# MCU_-_Peripherals.net
KiCad netlist of a schematic drawn in Altium Designer
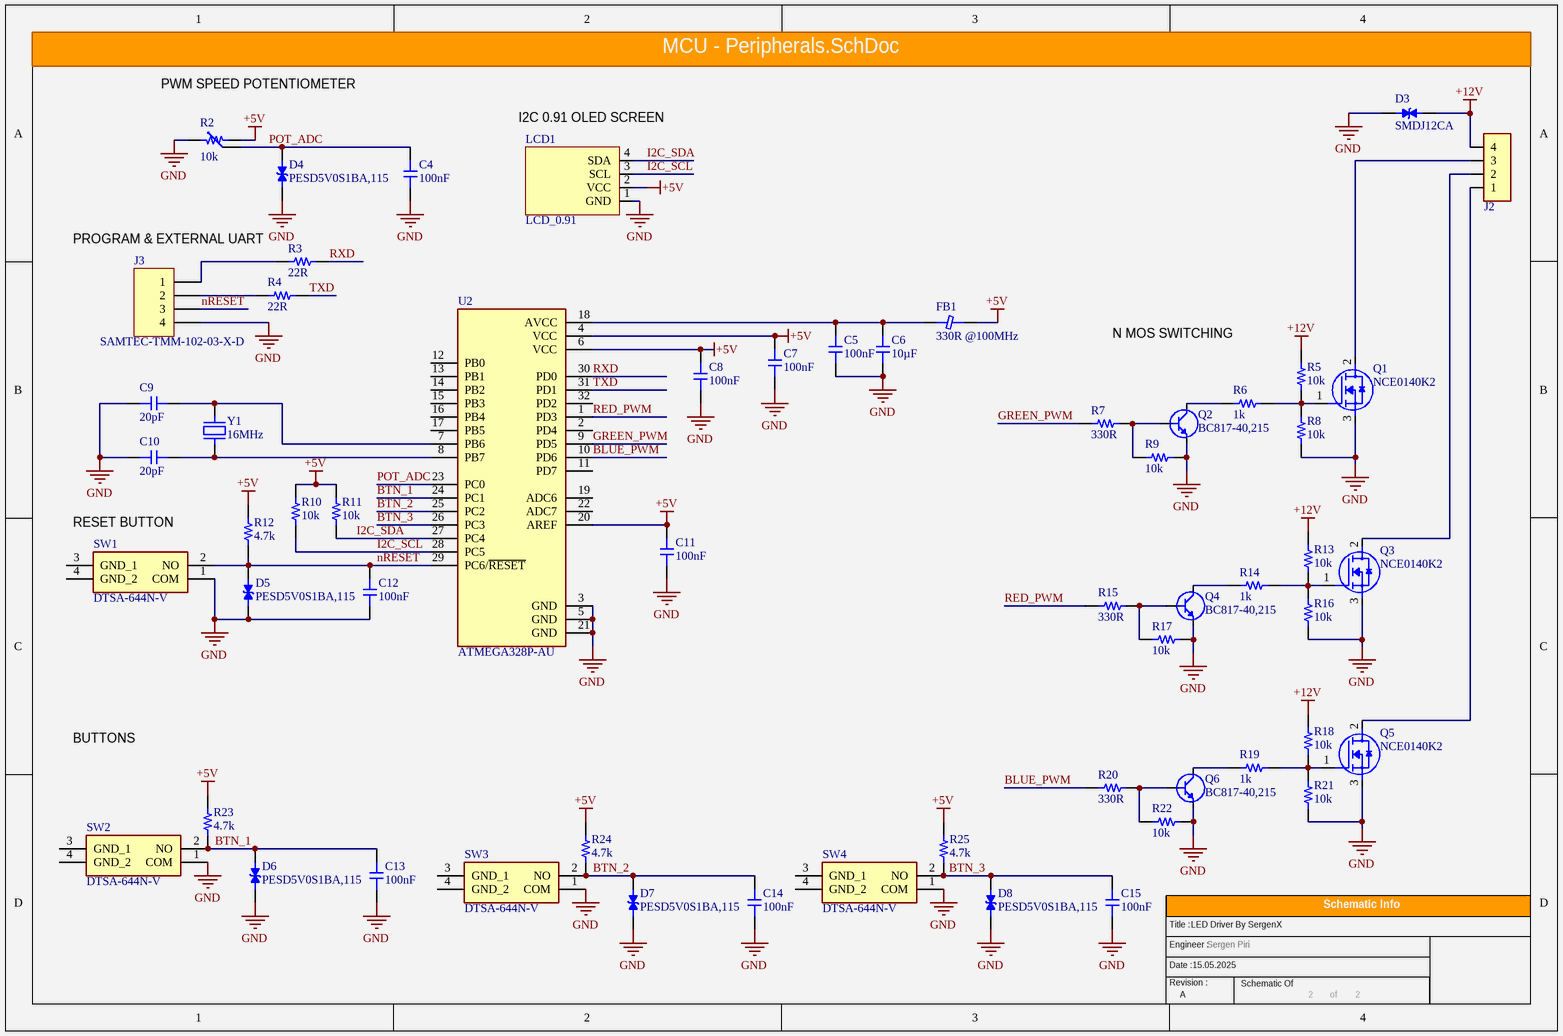
[diagram p0: MCU - Peripherals.SchDoc]

(export (version "E")
  (design (tool "Eeschema 10.0.6"))
  (components
    (comp (ref "C4")
      (value "100nF")
      (footprint "0402_CAP")
      (description "MLCC (1005) 0402 100nF 16VDC ±10% X7R")
      (libsource (lib "MainLibrary") (part "CL05B104KO5NNNC"))
    )
    (comp (ref "C5")
      (value "100nF")
      (footprint "0402_CAP")
      (description "MLCC (1005) 0402 100nF 16VDC ±10% X7R")
      (libsource (lib "MainLibrary") (part "CL05B104KO5NNNC"))
    )
    (comp (ref "C6")
      (value "10µF")
      (footprint "0805")
      (description "MLCC (2012) 0805 10uF 35VDC ±10% X6S")
      (libsource (lib "MainLibrary") (part "GRM21BC8YA106KE11L_1"))
    )
    (comp (ref "C7")
      (value "100nF")
      (footprint "0402_CAP")
      (description "MLCC (1005) 0402 100nF 16VDC ±10% X7R")
      (libsource (lib "MainLibrary") (part "CL05B104KO5NNNC"))
    )
    (comp (ref "C8")
      (value "100nF")
      (footprint "0402_CAP")
      (description "MLCC (1005) 0402 100nF 16VDC ±10% X7R")
      (libsource (lib "MainLibrary") (part "CL05B104KO5NNNC"))
    )
    (comp (ref "C9")
      (value "20pF")
      (footprint "0402_CAP")
      (description "MLCC (1005) 0402 20pF 50VDC ±5% C0G (NP0)")
      (libsource (lib "MainLibrary") (part "CL05C200JB5NNNC"))
    )
    (comp (ref "C10")
      (value "20pF")
      (footprint "0402_CAP")
      (description "MLCC (1005) 0402 20pF 50VDC ±5% C0G (NP0)")
      (libsource (lib "MainLibrary") (part "CL05C200JB5NNNC"))
    )
    (comp (ref "C11")
      (value "100nF")
      (footprint "0402_CAP")
      (description "MLCC (1005) 0402 100nF 16VDC ±10% X7R")
      (libsource (lib "MainLibrary") (part "CL05B104KO5NNNC"))
    )
    (comp (ref "C12")
      (value "100nF")
      (footprint "0402_CAP")
      (description "MLCC (1005) 0402 100nF 16VDC ±10% X7R")
      (libsource (lib "MainLibrary") (part "CL05B104KO5NNNC"))
    )
    (comp (ref "C13")
      (value "100nF")
      (footprint "0402_CAP")
      (description "MLCC (1005) 0402 100nF 16VDC ±10% X7R")
      (libsource (lib "MainLibrary") (part "CL05B104KO5NNNC"))
    )
    (comp (ref "C14")
      (value "100nF")
      (footprint "0402_CAP")
      (description "MLCC (1005) 0402 100nF 16VDC ±10% X7R")
      (libsource (lib "MainLibrary") (part "CL05B104KO5NNNC"))
    )
    (comp (ref "C15")
      (value "100nF")
      (footprint "0402_CAP")
      (description "MLCC (1005) 0402 100nF 16VDC ±10% X7R")
      (libsource (lib "MainLibrary") (part "CL05B104KO5NNNC"))
    )
    (comp (ref "D3")
      (value "SMDJ12CA")
      (footprint "MainLibrary:DIOM6859X262N")
      (description "150.8A 14.7V 12V SMC ESD and Surge Protection (TVS/ESD) ROHS")
      (fields (field (name "MP") "SMDJ36CA"))
      (libsource (lib "MainLibrary") (part "SMDJ12CA"))
    )
    (comp (ref "D4")
      (value "PESD5V0S1BA,115")
      (footprint "SOD323")
      (description "12A 130W 14V 5.5V Bidirectional 5V SOD-323 ESD and Surge Protection (TVS/ESD) ROHS")
      (fields
        (field (name "MANUFACTURER_PART_NUMBER") "LTST-C190KRKT")
        (field (name "MOUSER PART NUMBER") "859-LTST-C190KRKT")
      )
      (libsource (lib "MainLibrary") (part "PESD5V0S1BA,115"))
    )
    (comp (ref "D5")
      (value "PESD5V0S1BA,115")
      (footprint "SOD323")
      (description "12A 130W 14V 5.5V Bidirectional 5V SOD-323 ESD and Surge Protection (TVS/ESD) ROHS")
      (fields
        (field (name "MANUFACTURER_PART_NUMBER") "LTST-C190KRKT")
        (field (name "MOUSER PART NUMBER") "859-LTST-C190KRKT")
      )
      (libsource (lib "MainLibrary") (part "PESD5V0S1BA,115"))
    )
    (comp (ref "D6")
      (value "PESD5V0S1BA,115")
      (footprint "SOD323")
      (description "12A 130W 14V 5.5V Bidirectional 5V SOD-323 ESD and Surge Protection (TVS/ESD) ROHS")
      (fields
        (field (name "MANUFACTURER_PART_NUMBER") "LTST-C190KRKT")
        (field (name "MOUSER PART NUMBER") "859-LTST-C190KRKT")
      )
      (libsource (lib "MainLibrary") (part "PESD5V0S1BA,115"))
    )
    (comp (ref "D7")
      (value "PESD5V0S1BA,115")
      (footprint "SOD323")
      (description "12A 130W 14V 5.5V Bidirectional 5V SOD-323 ESD and Surge Protection (TVS/ESD) ROHS")
      (fields
        (field (name "MANUFACTURER_PART_NUMBER") "LTST-C190KRKT")
        (field (name "MOUSER PART NUMBER") "859-LTST-C190KRKT")
      )
      (libsource (lib "MainLibrary") (part "PESD5V0S1BA,115"))
    )
    (comp (ref "D8")
      (value "PESD5V0S1BA,115")
      (footprint "SOD323")
      (description "12A 130W 14V 5.5V Bidirectional 5V SOD-323 ESD and Surge Protection (TVS/ESD) ROHS")
      (fields
        (field (name "MANUFACTURER_PART_NUMBER") "LTST-C190KRKT")
        (field (name "MOUSER PART NUMBER") "859-LTST-C190KRKT")
      )
      (libsource (lib "MainLibrary") (part "PESD5V0S1BA,115"))
    )
    (comp (ref "FB1")
      (value "330R @100MHz")
      (footprint "Inductor-0805")
      (description "FERRITE BEAD 0603 330R/100MHZ SMD")
      (libsource (lib "MainLibrary") (part "LCB2012-152Y-N"))
    )
    (comp (ref "J2")
      (value "691322310004")
      (footprint "691322310004")
      (description "WURTH 3.81MM Terminal Block 691322310004")
      (libsource (lib "MainLibrary") (part "691322310004"))
    )
    (comp (ref "J3")
      (value "SAMTEC-TMM-102-03-X-D")
      (footprint "MainLibrary:SAMTEC-TMM-102-03-X-D")
      (description "CONN HEADER VERT 4POS 2MM")
      (libsource (lib "MainLibrary") (part "SAMTEC-TMM-102-03-X-D"))
    )
    (comp (ref "LCD1")
      (value "LCD_0.91")
      (footprint "0_91-OLED")
      (libsource (lib "MainLibrary") (part "LCD_0.91"))
    )
    (comp (ref "Q1")
      (value "NCE0140K2")
      (footprint "TO-252")
      (description "100V 40A 17mΩ@10V,28A 140W 3V 1 N-channel TO-252 MOSFETs ROHS")
      (libsource (lib "MainLibrary") (part "NCE0140K2"))
    )
    (comp (ref "Q2")
      (value "BC817-40,215")
      (footprint "BC81740215")
      (description "0.5A 45V BJT NPN Transistor SOT23 SMD")
      (fields (field (name "MOUSER PART NUMBER") "771-BC817-40-T/R"))
      (libsource (lib "MainLibrary") (part "BC817-40,215"))
    )
    (comp (ref "Q3")
      (value "NCE0140K2")
      (footprint "TO-252")
      (description "100V 40A 17mΩ@10V,28A 140W 3V 1 N-channel TO-252 MOSFETs ROHS")
      (libsource (lib "MainLibrary") (part "NCE0140K2"))
    )
    (comp (ref "Q4")
      (value "BC817-40,215")
      (footprint "BC81740215")
      (description "0.5A 45V BJT NPN Transistor SOT23 SMD")
      (fields (field (name "MOUSER PART NUMBER") "771-BC817-40-T/R"))
      (libsource (lib "MainLibrary") (part "BC817-40,215"))
    )
    (comp (ref "Q5")
      (value "NCE0140K2")
      (footprint "TO-252")
      (description "100V 40A 17mΩ@10V,28A 140W 3V 1 N-channel TO-252 MOSFETs ROHS")
      (libsource (lib "MainLibrary") (part "NCE0140K2"))
    )
    (comp (ref "Q6")
      (value "BC817-40,215")
      (footprint "BC81740215")
      (description "0.5A 45V BJT NPN Transistor SOT23 SMD")
      (fields (field (name "MOUSER PART NUMBER") "771-BC817-40-T/R"))
      (libsource (lib "MainLibrary") (part "BC817-40,215"))
    )
    (comp (ref "R2")
      (value "10k")
      (footprint "POT_ROTARY")
      (description "10k DIP")
      (libsource (lib "MainLibrary") (part "Rotary Generic Potentiometer"))
    )
    (comp (ref "R3")
      (value "22R")
      (footprint "0402_RES")
      (description "RES.(1005) 0402 22 Ohms 1% 1/16W AEC-Q200")
      (libsource (lib "MainLibrary") (part "AC0402FR-0722RL"))
    )
    (comp (ref "R4")
      (value "22R")
      (footprint "0402_RES")
      (description "RES.(1005) 0402 22 Ohms 1% 1/16W AEC-Q200")
      (libsource (lib "MainLibrary") (part "AC0402FR-0722RL"))
    )
    (comp (ref "R5")
      (value "10k")
      (footprint "0402_RES")
      (description "RES.(1005) 0402 10K Ohms 1% 1/16W")
      (libsource (lib "MainLibrary") (part "AC0402FR-0710KL"))
    )
    (comp (ref "R6")
      (value "1k")
      (footprint "0402_RES")
      (description "RES.(1005) 0402 1K Ohms 1% 1/16W 100PPM AEC-Q200 S")
      (libsource (lib "MainLibrary") (part "AC0402FR-071KL"))
    )
    (comp (ref "R7")
      (value "330R")
      (footprint "0402_RES")
      (description "RES.(1005) 0402 330 Ohms 1% 1/16W 100PPM")
      (libsource (lib "MainLibrary") (part "CRCW0402330RFKTDBC"))
    )
    (comp (ref "R8")
      (value "10k")
      (footprint "0402_RES")
      (description "RES.(1005) 0402 10K Ohms 1% 1/16W")
      (libsource (lib "MainLibrary") (part "AC0402FR-0710KL"))
    )
    (comp (ref "R9")
      (value "10k")
      (footprint "0402_RES")
      (description "RES.(1005) 0402 10K Ohms 1% 1/16W")
      (libsource (lib "MainLibrary") (part "AC0402FR-0710KL"))
    )
    (comp (ref "R10")
      (value "10k")
      (footprint "0402_RES")
      (description "RES.(1005) 0402 10K Ohms 1% 1/16W")
      (libsource (lib "MainLibrary") (part "AC0402FR-0710KL"))
    )
    (comp (ref "R11")
      (value "10k")
      (footprint "0402_RES")
      (description "RES.(1005) 0402 10K Ohms 1% 1/16W")
      (libsource (lib "MainLibrary") (part "AC0402FR-0710KL"))
    )
    (comp (ref "R12")
      (value "4.7k")
      (footprint "0402_RES")
      (description "RES.(1005) 0402 4.7K Ohms 1% 1/16W 100PPM AEC-Q200")
      (libsource (lib "MainLibrary") (part "AC0402FR-074K7L"))
    )
    (comp (ref "R13")
      (value "10k")
      (footprint "0402_RES")
      (description "RES.(1005) 0402 10K Ohms 1% 1/16W")
      (libsource (lib "MainLibrary") (part "AC0402FR-0710KL"))
    )
    (comp (ref "R14")
      (value "1k")
      (footprint "0402_RES")
      (description "RES.(1005) 0402 1K Ohms 1% 1/16W 100PPM AEC-Q200 S")
      (libsource (lib "MainLibrary") (part "AC0402FR-071KL"))
    )
    (comp (ref "R15")
      (value "330R")
      (footprint "0402_RES")
      (description "RES.(1005) 0402 330 Ohms 1% 1/16W 100PPM")
      (libsource (lib "MainLibrary") (part "CRCW0402330RFKTDBC"))
    )
    (comp (ref "R16")
      (value "10k")
      (footprint "0402_RES")
      (description "RES.(1005) 0402 10K Ohms 1% 1/16W")
      (libsource (lib "MainLibrary") (part "AC0402FR-0710KL"))
    )
    (comp (ref "R17")
      (value "10k")
      (footprint "0402_RES")
      (description "RES.(1005) 0402 10K Ohms 1% 1/16W")
      (libsource (lib "MainLibrary") (part "AC0402FR-0710KL"))
    )
    (comp (ref "R18")
      (value "10k")
      (footprint "0402_RES")
      (description "RES.(1005) 0402 10K Ohms 1% 1/16W")
      (libsource (lib "MainLibrary") (part "AC0402FR-0710KL"))
    )
    (comp (ref "R19")
      (value "1k")
      (footprint "0402_RES")
      (description "RES.(1005) 0402 1K Ohms 1% 1/16W 100PPM AEC-Q200 S")
      (libsource (lib "MainLibrary") (part "AC0402FR-071KL"))
    )
    (comp (ref "R20")
      (value "330R")
      (footprint "0402_RES")
      (description "RES.(1005) 0402 330 Ohms 1% 1/16W 100PPM")
      (libsource (lib "MainLibrary") (part "CRCW0402330RFKTDBC"))
    )
    (comp (ref "R21")
      (value "10k")
      (footprint "0402_RES")
      (description "RES.(1005) 0402 10K Ohms 1% 1/16W")
      (libsource (lib "MainLibrary") (part "AC0402FR-0710KL"))
    )
    (comp (ref "R22")
      (value "10k")
      (footprint "0402_RES")
      (description "RES.(1005) 0402 10K Ohms 1% 1/16W")
      (libsource (lib "MainLibrary") (part "AC0402FR-0710KL"))
    )
    (comp (ref "R23")
      (value "4.7k")
      (footprint "0402_RES")
      (description "RES.(1005) 0402 4.7K Ohms 1% 1/16W 100PPM AEC-Q200")
      (libsource (lib "MainLibrary") (part "AC0402FR-074K7L"))
    )
    (comp (ref "R24")
      (value "4.7k")
      (footprint "0402_RES")
      (description "RES.(1005) 0402 4.7K Ohms 1% 1/16W 100PPM AEC-Q200")
      (libsource (lib "MainLibrary") (part "AC0402FR-074K7L"))
    )
    (comp (ref "R25")
      (value "4.7k")
      (footprint "0402_RES")
      (description "RES.(1005) 0402 4.7K Ohms 1% 1/16W 100PPM AEC-Q200")
      (libsource (lib "MainLibrary") (part "AC0402FR-074K7L"))
    )
    (comp (ref "SW1")
      (value "DTSA-644N-V")
      (footprint "DTSA644NV")
      (description "Button DIP")
      (fields (field (name "MOUSER PART NUMBER") "113-DTSA-644N-V"))
      (libsource (lib "MainLibrary") (part "DTSA-644N-V"))
    )
    (comp (ref "SW2")
      (value "DTSA-644N-V")
      (footprint "DTSA644NV")
      (description "Button DIP")
      (fields (field (name "MOUSER PART NUMBER") "113-DTSA-644N-V"))
      (libsource (lib "MainLibrary") (part "DTSA-644N-V"))
    )
    (comp (ref "SW3")
      (value "DTSA-644N-V")
      (footprint "DTSA644NV")
      (description "Button DIP")
      (fields (field (name "MOUSER PART NUMBER") "113-DTSA-644N-V"))
      (libsource (lib "MainLibrary") (part "DTSA-644N-V"))
    )
    (comp (ref "SW4")
      (value "DTSA-644N-V")
      (footprint "DTSA644NV")
      (description "Button DIP")
      (fields (field (name "MOUSER PART NUMBER") "113-DTSA-644N-V"))
      (libsource (lib "MainLibrary") (part "DTSA-644N-V"))
    )
    (comp (ref "U2")
      (value "ATMEGA328P-AU")
      (footprint "QFP80P900X900X120-32N")
      (description "AVR AVRÂ® ATmega Microcontroller IC 8-Bit 20MHz 32KB (16K x 16) FLASH 32-TQFP (7x7)")
      (fields (field (name "MF") "Microchip"))
      (libsource (lib "MainLibrary") (part "ATMEGA328P-AU"))
    )
    (comp (ref "Y1")
      (value "16MHz")
      (footprint "HC49S")
      (description "CRYSTAL 16MHz 20pF SMD")
      (libsource (lib "MainLibrary") (part "AS49SD-16M-FE200F3"))
    )
  )
  (nets
    (net (code "1") (name "+5V") (class "Default")
      (node (ref "C11") (pin "2") (pinfunction "2_2") (pintype "passive"))
      (node (ref "C7") (pin "2") (pinfunction "2_2") (pintype "passive"))
      (node (ref "C8") (pin "2") (pinfunction "2_2") (pintype "passive"))
      (node (ref "FB1") (pin "2") (pinfunction "2_2") (pintype "passive"))
      (node (ref "LCD1") (pin "2") (pinfunction "VCC_2") (pintype "passive"))
      (node (ref "R10") (pin "2") (pinfunction "2_2") (pintype "passive"))
      (node (ref "R11") (pin "2") (pinfunction "2_2") (pintype "passive"))
      (node (ref "R12") (pin "2") (pinfunction "2_2") (pintype "passive"))
      (node (ref "R2") (pin "1") (pinfunction "1_1") (pintype "passive"))
      (node (ref "R23") (pin "1") (pinfunction "1_1") (pintype "passive"))
      (node (ref "R24") (pin "1") (pinfunction "1_1") (pintype "passive"))
      (node (ref "R25") (pin "1") (pinfunction "1_1") (pintype "passive"))
      (node (ref "U2") (pin "20") (pinfunction "AREF_20") (pintype "passive"))
      (node (ref "U2") (pin "4") (pinfunction "VCC_4") (pintype "power_in"))
      (node (ref "U2") (pin "6") (pinfunction "VCC_6") (pintype "power_in"))
    )
    (net (code "2") (name "+12V") (class "Default")
      (node (ref "D3") (pin "1") (pinfunction "1_1") (pintype "passive"))
      (node (ref "J2") (pin "4") (pinfunction "4_4") (pintype "passive"))
      (node (ref "R13") (pin "2") (pinfunction "2_2") (pintype "passive"))
      (node (ref "R18") (pin "2") (pinfunction "2_2") (pintype "passive"))
      (node (ref "R5") (pin "2") (pinfunction "2_2") (pintype "passive"))
    )
    (net (code "3") (name "/BLUE_PWM") (class "Default")
      (node (ref "R20") (pin "1") (pinfunction "1_1") (pintype "passive"))
      (node (ref "U2") (pin "10") (pinfunction "PD6_10") (pintype "passive"))
    )
    (net (code "4") (name "/BTN_1") (class "Default")
      (node (ref "C13") (pin "2") (pinfunction "2_2") (pintype "passive"))
      (node (ref "D6") (pin "C") (pinfunction "C_C") (pintype "passive"))
      (node (ref "R23") (pin "2") (pinfunction "2_2") (pintype "passive"))
      (node (ref "SW2") (pin "2") (pinfunction "NO_2") (pintype "passive"))
      (node (ref "U2") (pin "24") (pinfunction "PC1_24") (pintype "passive"))
    )
    (net (code "5") (name "/BTN_2") (class "Default")
      (node (ref "C14") (pin "2") (pinfunction "2_2") (pintype "passive"))
      (node (ref "D7") (pin "C") (pinfunction "C_C") (pintype "passive"))
      (node (ref "R24") (pin "2") (pinfunction "2_2") (pintype "passive"))
      (node (ref "SW3") (pin "2") (pinfunction "NO_2") (pintype "passive"))
      (node (ref "U2") (pin "25") (pinfunction "PC2_25") (pintype "passive"))
    )
    (net (code "6") (name "/BTN_3") (class "Default")
      (node (ref "C15") (pin "2") (pinfunction "2_2") (pintype "passive"))
      (node (ref "D8") (pin "C") (pinfunction "C_C") (pintype "passive"))
      (node (ref "R25") (pin "2") (pinfunction "2_2") (pintype "passive"))
      (node (ref "SW4") (pin "2") (pinfunction "NO_2") (pintype "passive"))
      (node (ref "U2") (pin "26") (pinfunction "PC3_26") (pintype "passive"))
    )
    (net (code "7") (name "/GREEN_PWM") (class "Default")
      (node (ref "R7") (pin "1") (pinfunction "1_1") (pintype "passive"))
      (node (ref "U2") (pin "9") (pinfunction "PD5_9") (pintype "passive"))
    )
    (net (code "8") (name "/I2C_SCL") (class "Default")
      (node (ref "LCD1") (pin "3") (pinfunction "SCL_3") (pintype "passive"))
      (node (ref "R10") (pin "1") (pinfunction "1_1") (pintype "passive"))
      (node (ref "U2") (pin "28") (pinfunction "PC5_28") (pintype "passive"))
    )
    (net (code "9") (name "/I2C_SDA") (class "Default")
      (node (ref "LCD1") (pin "4") (pinfunction "SDA_4") (pintype "passive"))
      (node (ref "R11") (pin "1") (pinfunction "1_1") (pintype "passive"))
      (node (ref "U2") (pin "27") (pinfunction "PC4_27") (pintype "passive"))
    )
    (net (code "10") (name "/POT_ADC") (class "Default")
      (node (ref "C4") (pin "2") (pinfunction "2_2") (pintype "passive"))
      (node (ref "D4") (pin "C") (pinfunction "C_C") (pintype "passive"))
      (node (ref "R2") (pin "2") (pinfunction "2_2") (pintype "passive"))
      (node (ref "U2") (pin "23") (pinfunction "PC0_23") (pintype "passive"))
    )
    (net (code "11") (name "/RED_PWM") (class "Default")
      (node (ref "R15") (pin "1") (pinfunction "1_1") (pintype "passive"))
      (node (ref "U2") (pin "1") (pinfunction "PD3_1") (pintype "passive"))
    )
    (net (code "12") (name "/RXD") (class "Default")
      (node (ref "R3") (pin "2") (pinfunction "2_2") (pintype "passive"))
      (node (ref "U2") (pin "30") (pinfunction "PD0_30") (pintype "passive"))
    )
    (net (code "13") (name "/TXD") (class "Default")
      (node (ref "R4") (pin "2") (pinfunction "2_2") (pintype "passive"))
      (node (ref "U2") (pin "31") (pinfunction "PD1_31") (pintype "passive"))
    )
    (net (code "14") (name "/nRESET") (class "Default")
      (node (ref "C12") (pin "2") (pinfunction "2_2") (pintype "passive"))
      (node (ref "D5") (pin "C") (pinfunction "C_C") (pintype "passive"))
      (node (ref "J3") (pin "3") (pinfunction "3_3") (pintype "passive"))
      (node (ref "R12") (pin "1") (pinfunction "1_1") (pintype "passive"))
      (node (ref "SW1") (pin "2") (pinfunction "NO_2") (pintype "passive"))
      (node (ref "U2") (pin "29") (pinfunction "PC6/~{RESET}_29") (pintype "passive"))
    )
    (net (code "15") (name "GND") (class "Default")
      (node (ref "C10") (pin "2") (pinfunction "2_2") (pintype "passive"))
      (node (ref "C11") (pin "1") (pinfunction "1_1") (pintype "passive"))
      (node (ref "C12") (pin "1") (pinfunction "1_1") (pintype "passive"))
      (node (ref "C13") (pin "1") (pinfunction "1_1") (pintype "passive"))
      (node (ref "C14") (pin "1") (pinfunction "1_1") (pintype "passive"))
      (node (ref "C15") (pin "1") (pinfunction "1_1") (pintype "passive"))
      (node (ref "C4") (pin "1") (pinfunction "1_1") (pintype "passive"))
      (node (ref "C5") (pin "1") (pinfunction "1_1") (pintype "passive"))
      (node (ref "C6") (pin "1") (pinfunction "1_1") (pintype "passive"))
      (node (ref "C7") (pin "1") (pinfunction "1_1") (pintype "passive"))
      (node (ref "C8") (pin "1") (pinfunction "1_1") (pintype "passive"))
      (node (ref "C9") (pin "2") (pinfunction "2_2") (pintype "passive"))
      (node (ref "D3") (pin "2") (pinfunction "2_2") (pintype "passive"))
      (node (ref "D4") (pin "A") (pinfunction "A_A") (pintype "passive"))
      (node (ref "D5") (pin "A") (pinfunction "A_A") (pintype "passive"))
      (node (ref "D6") (pin "A") (pinfunction "A_A") (pintype "passive"))
      (node (ref "D7") (pin "A") (pinfunction "A_A") (pintype "passive"))
      (node (ref "D8") (pin "A") (pinfunction "A_A") (pintype "passive"))
      (node (ref "J3") (pin "4") (pinfunction "4_4") (pintype "passive"))
      (node (ref "LCD1") (pin "1") (pinfunction "GND_1") (pintype "passive"))
      (node (ref "Q1") (pin "3") (pinfunction "S_3") (pintype "passive"))
      (node (ref "Q2") (pin "2") (pinfunction "E_2") (pintype "passive"))
      (node (ref "Q3") (pin "3") (pinfunction "S_3") (pintype "passive"))
      (node (ref "Q4") (pin "2") (pinfunction "E_2") (pintype "passive"))
      (node (ref "Q5") (pin "3") (pinfunction "S_3") (pintype "passive"))
      (node (ref "Q6") (pin "2") (pinfunction "E_2") (pintype "passive"))
      (node (ref "R16") (pin "1") (pinfunction "1_1") (pintype "passive"))
      (node (ref "R17") (pin "1") (pinfunction "1_1") (pintype "passive"))
      (node (ref "R2") (pin "3") (pinfunction "3_3") (pintype "passive"))
      (node (ref "R21") (pin "1") (pinfunction "1_1") (pintype "passive"))
      (node (ref "R22") (pin "1") (pinfunction "1_1") (pintype "passive"))
      (node (ref "R8") (pin "1") (pinfunction "1_1") (pintype "passive"))
      (node (ref "R9") (pin "1") (pinfunction "1_1") (pintype "passive"))
      (node (ref "SW1") (pin "1") (pinfunction "COM_1") (pintype "passive"))
      (node (ref "SW2") (pin "1") (pinfunction "COM_1") (pintype "passive"))
      (node (ref "SW3") (pin "1") (pinfunction "COM_1") (pintype "passive"))
      (node (ref "SW4") (pin "1") (pinfunction "COM_1") (pintype "passive"))
      (node (ref "U2") (pin "21") (pinfunction "GND_21") (pintype "power_in"))
      (node (ref "U2") (pin "3") (pinfunction "GND_3") (pintype "power_in"))
      (node (ref "U2") (pin "5") (pinfunction "GND_5") (pintype "power_in"))
    )
    (net (code "16") (name "Net-(J3-Pad1)") (class "Default")
      (node (ref "J3") (pin "1") (pinfunction "1_1") (pintype "passive"))
      (node (ref "R3") (pin "1") (pinfunction "1_1") (pintype "passive"))
    )
    (net (code "17") (name "Net-(J3-Pad2)") (class "Default")
      (node (ref "J3") (pin "2") (pinfunction "2_2") (pintype "passive"))
      (node (ref "R4") (pin "1") (pinfunction "1_1") (pintype "passive"))
    )
    (net (code "18") (name "Net-(Q1-D)") (class "Default")
      (node (ref "J2") (pin "3") (pinfunction "3_3") (pintype "passive"))
      (node (ref "Q1") (pin "2") (pinfunction "D_2") (pintype "passive"))
    )
    (net (code "19") (name "Net-(Q1-G)") (class "Default")
      (node (ref "Q1") (pin "1") (pinfunction "G_1") (pintype "passive"))
      (node (ref "R5") (pin "1") (pinfunction "1_1") (pintype "passive"))
      (node (ref "R6") (pin "2") (pinfunction "2_2") (pintype "passive"))
      (node (ref "R8") (pin "2") (pinfunction "2_2") (pintype "passive"))
    )
    (net (code "20") (name "Net-(Q2-B)") (class "Default")
      (node (ref "Q2") (pin "1") (pinfunction "B_1") (pintype "passive"))
      (node (ref "R7") (pin "2") (pinfunction "2_2") (pintype "passive"))
      (node (ref "R9") (pin "2") (pinfunction "2_2") (pintype "passive"))
    )
    (net (code "21") (name "Net-(Q2-C)") (class "Default")
      (node (ref "Q2") (pin "3") (pinfunction "C_3") (pintype "passive"))
      (node (ref "R6") (pin "1") (pinfunction "1_1") (pintype "passive"))
    )
    (net (code "22") (name "Net-(Q3-D)") (class "Default")
      (node (ref "J2") (pin "2") (pinfunction "2_2") (pintype "passive"))
      (node (ref "Q3") (pin "2") (pinfunction "D_2") (pintype "passive"))
    )
    (net (code "23") (name "Net-(Q3-G)") (class "Default")
      (node (ref "Q3") (pin "1") (pinfunction "G_1") (pintype "passive"))
      (node (ref "R13") (pin "1") (pinfunction "1_1") (pintype "passive"))
      (node (ref "R14") (pin "2") (pinfunction "2_2") (pintype "passive"))
      (node (ref "R16") (pin "2") (pinfunction "2_2") (pintype "passive"))
    )
    (net (code "24") (name "Net-(Q4-B)") (class "Default")
      (node (ref "Q4") (pin "1") (pinfunction "B_1") (pintype "passive"))
      (node (ref "R15") (pin "2") (pinfunction "2_2") (pintype "passive"))
      (node (ref "R17") (pin "2") (pinfunction "2_2") (pintype "passive"))
    )
    (net (code "25") (name "Net-(Q4-C)") (class "Default")
      (node (ref "Q4") (pin "3") (pinfunction "C_3") (pintype "passive"))
      (node (ref "R14") (pin "1") (pinfunction "1_1") (pintype "passive"))
    )
    (net (code "26") (name "Net-(Q5-D)") (class "Default")
      (node (ref "J2") (pin "1") (pinfunction "1_1") (pintype "passive"))
      (node (ref "Q5") (pin "2") (pinfunction "D_2") (pintype "passive"))
    )
    (net (code "27") (name "Net-(Q5-G)") (class "Default")
      (node (ref "Q5") (pin "1") (pinfunction "G_1") (pintype "passive"))
      (node (ref "R18") (pin "1") (pinfunction "1_1") (pintype "passive"))
      (node (ref "R19") (pin "2") (pinfunction "2_2") (pintype "passive"))
      (node (ref "R21") (pin "2") (pinfunction "2_2") (pintype "passive"))
    )
    (net (code "28") (name "Net-(Q6-B)") (class "Default")
      (node (ref "Q6") (pin "1") (pinfunction "B_1") (pintype "passive"))
      (node (ref "R20") (pin "2") (pinfunction "2_2") (pintype "passive"))
      (node (ref "R22") (pin "2") (pinfunction "2_2") (pintype "passive"))
    )
    (net (code "29") (name "Net-(Q6-C)") (class "Default")
      (node (ref "Q6") (pin "3") (pinfunction "C_3") (pintype "passive"))
      (node (ref "R19") (pin "1") (pinfunction "1_1") (pintype "passive"))
    )
    (net (code "30") (name "Net-(U2-AVCC)") (class "Default")
      (node (ref "C5") (pin "2") (pinfunction "2_2") (pintype "passive"))
      (node (ref "C6") (pin "2") (pinfunction "2_2") (pintype "passive"))
      (node (ref "FB1") (pin "1") (pinfunction "1_1") (pintype "passive"))
      (node (ref "U2") (pin "18") (pinfunction "AVCC_18") (pintype "power_in"))
    )
    (net (code "31") (name "Net-(U2-PB6)") (class "Default")
      (node (ref "C9") (pin "1") (pinfunction "1_1") (pintype "passive"))
      (node (ref "U2") (pin "7") (pinfunction "PB6_7") (pintype "passive"))
      (node (ref "Y1") (pin "2") (pinfunction "2_2") (pintype "passive"))
    )
    (net (code "32") (name "Net-(U2-PB7)") (class "Default")
      (node (ref "C10") (pin "1") (pinfunction "1_1") (pintype "passive"))
      (node (ref "U2") (pin "8") (pinfunction "PB7_8") (pintype "passive"))
      (node (ref "Y1") (pin "1") (pinfunction "1_1") (pintype "passive"))
    )
    (net (code "33") (name "unconnected-(SW1-GND_1-Pad3)") (class "Default")
      (node (ref "SW1") (pin "3") (pinfunction "GND_1_3") (pintype "passive"))
    )
    (net (code "34") (name "unconnected-(SW1-GND_2-Pad4)") (class "Default")
      (node (ref "SW1") (pin "4") (pinfunction "GND_2_4") (pintype "passive"))
    )
    (net (code "35") (name "unconnected-(SW2-GND_1-Pad3)") (class "Default")
      (node (ref "SW2") (pin "3") (pinfunction "GND_1_3") (pintype "passive"))
    )
    (net (code "36") (name "unconnected-(SW2-GND_2-Pad4)") (class "Default")
      (node (ref "SW2") (pin "4") (pinfunction "GND_2_4") (pintype "passive"))
    )
    (net (code "37") (name "unconnected-(SW3-GND_1-Pad3)") (class "Default")
      (node (ref "SW3") (pin "3") (pinfunction "GND_1_3") (pintype "passive"))
    )
    (net (code "38") (name "unconnected-(SW3-GND_2-Pad4)") (class "Default")
      (node (ref "SW3") (pin "4") (pinfunction "GND_2_4") (pintype "passive"))
    )
    (net (code "39") (name "unconnected-(SW4-GND_1-Pad3)") (class "Default")
      (node (ref "SW4") (pin "3") (pinfunction "GND_1_3") (pintype "passive"))
    )
    (net (code "40") (name "unconnected-(SW4-GND_2-Pad4)") (class "Default")
      (node (ref "SW4") (pin "4") (pinfunction "GND_2_4") (pintype "passive"))
    )
    (net (code "41") (name "unconnected-(U2-ADC6-Pad19)") (class "Default")
      (node (ref "U2") (pin "19") (pinfunction "ADC6_19") (pintype "passive"))
    )
    (net (code "42") (name "unconnected-(U2-ADC7-Pad22)") (class "Default")
      (node (ref "U2") (pin "22") (pinfunction "ADC7_22") (pintype "passive"))
    )
    (net (code "43") (name "unconnected-(U2-PB0-Pad12)") (class "Default")
      (node (ref "U2") (pin "12") (pinfunction "PB0_12") (pintype "passive"))
    )
    (net (code "44") (name "unconnected-(U2-PB1-Pad13)") (class "Default")
      (node (ref "U2") (pin "13") (pinfunction "PB1_13") (pintype "passive"))
    )
    (net (code "45") (name "unconnected-(U2-PB2-Pad14)") (class "Default")
      (node (ref "U2") (pin "14") (pinfunction "PB2_14") (pintype "passive"))
    )
    (net (code "46") (name "unconnected-(U2-PB3-Pad15)") (class "Default")
      (node (ref "U2") (pin "15") (pinfunction "PB3_15") (pintype "passive"))
    )
    (net (code "47") (name "unconnected-(U2-PB4-Pad16)") (class "Default")
      (node (ref "U2") (pin "16") (pinfunction "PB4_16") (pintype "passive"))
    )
    (net (code "48") (name "unconnected-(U2-PB5-Pad17)") (class "Default")
      (node (ref "U2") (pin "17") (pinfunction "PB5_17") (pintype "passive"))
    )
    (net (code "49") (name "unconnected-(U2-PD2-Pad32)") (class "Default")
      (node (ref "U2") (pin "32") (pinfunction "PD2_32") (pintype "passive"))
    )
    (net (code "50") (name "unconnected-(U2-PD4-Pad2)") (class "Default")
      (node (ref "U2") (pin "2") (pinfunction "PD4_2") (pintype "passive"))
    )
    (net (code "51") (name "unconnected-(U2-PD7-Pad11)") (class "Default")
      (node (ref "U2") (pin "11") (pinfunction "PD7_11") (pintype "passive"))
    )
  )
)
